# apricot.net
KiCad netlist of a schematic drawn in EAGLE
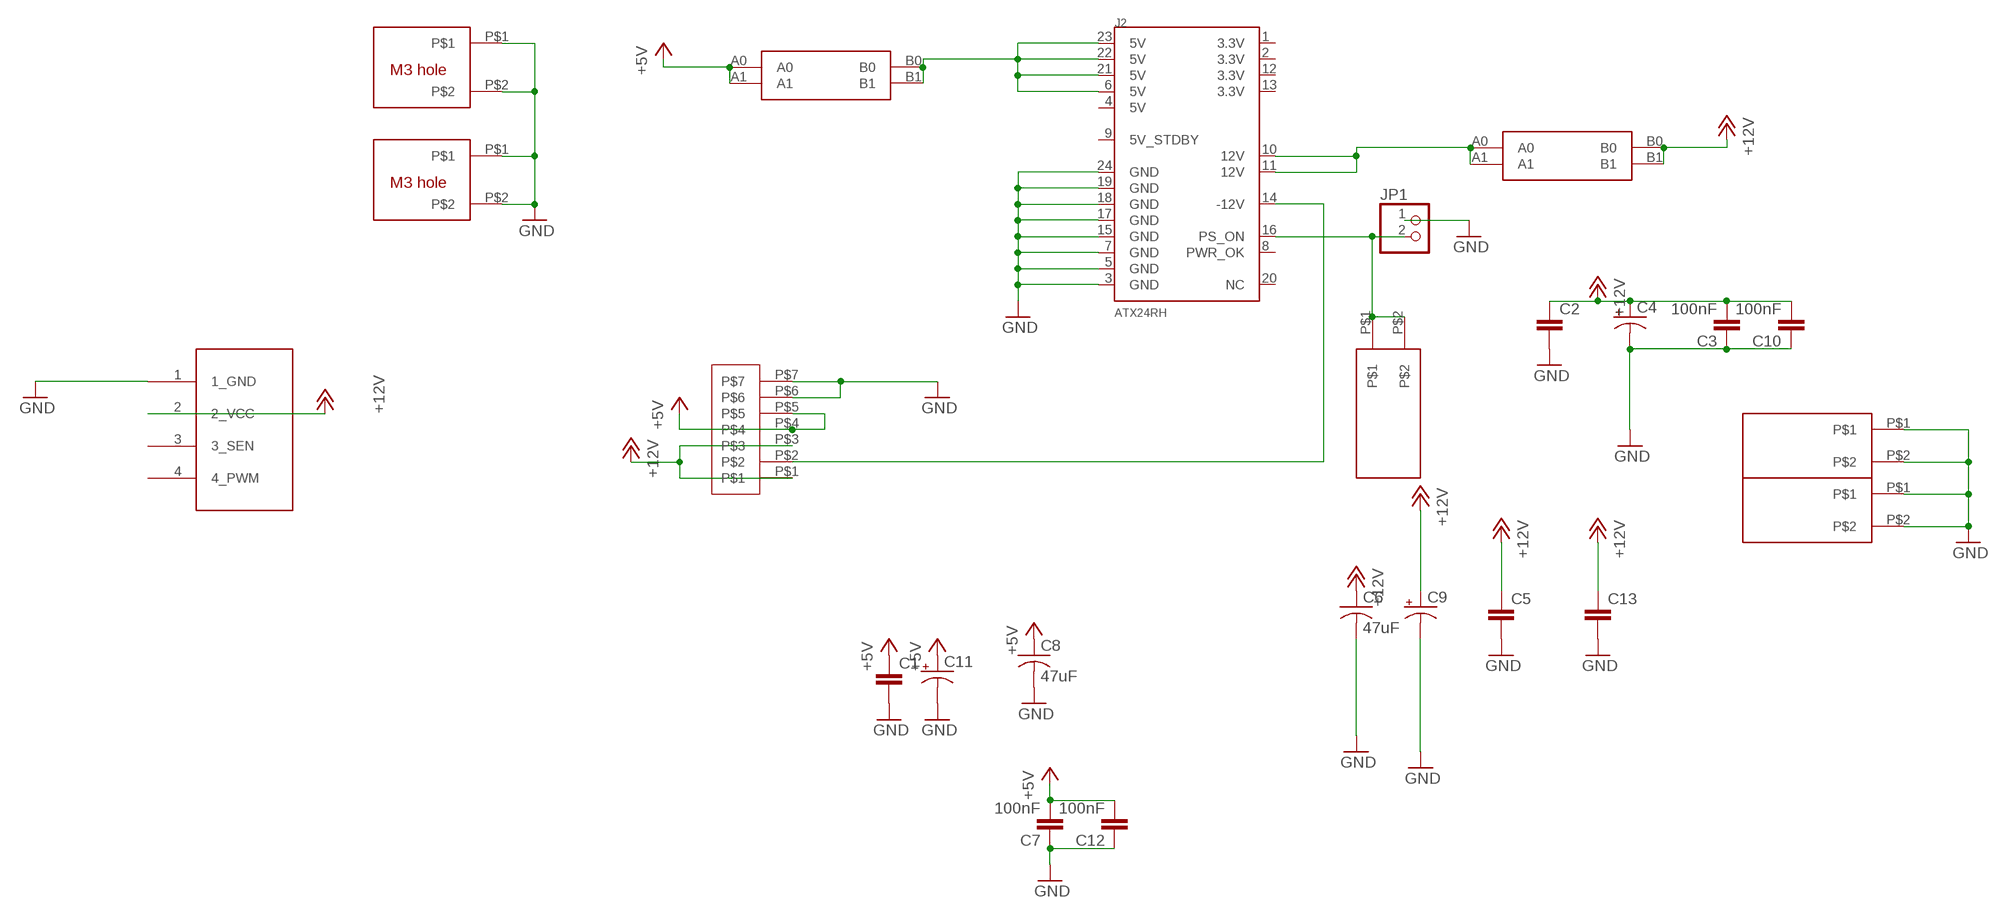
[diagram p0: schematic, sheet 1]

(export (version "E")
  (design (tool "Eeschema 10.0.6"))
  (components
    (comp (ref "C1")
      (value "C5/2.5")
      (footprint "eagle-import:C5B2.5")
      (libsource (lib "eagle-import") (part "C5/2.5"))
    )
    (comp (ref "C2")
      (value "C5/2.5")
      (footprint "eagle-import:C5B2.5")
      (libsource (lib "eagle-import") (part "C5/2.5"))
    )
    (comp (ref "C3")
      (value "100nF")
      (footprint "eagle-import:0805@1")
      (libsource (lib "eagle-import") (part "CAP0805"))
    )
    (comp (ref "C4")
      (value "CPOL-USE3.5-8")
      (footprint "eagle-import:E3,5-8")
      (libsource (lib "eagle-import") (part "CPOL-USE3.5-8"))
    )
    (comp (ref "C5")
      (value "C5/2.5")
      (footprint "eagle-import:C5B2.5")
      (libsource (lib "eagle-import") (part "C5/2.5"))
    )
    (comp (ref "C6")
      (value "47uF")
      (footprint "eagle-import:C1210")
      (libsource (lib "eagle-import") (part "C-USC1210"))
    )
    (comp (ref "C7")
      (value "100nF")
      (footprint "eagle-import:0805@1")
      (libsource (lib "eagle-import") (part "CAP0805"))
    )
    (comp (ref "C8")
      (value "47uF")
      (footprint "eagle-import:C1210")
      (libsource (lib "eagle-import") (part "C-USC1210"))
    )
    (comp (ref "C9")
      (value "CPOL-USE3.5-8")
      (footprint "eagle-import:E3,5-8")
      (libsource (lib "eagle-import") (part "CPOL-USE3.5-8"))
    )
    (comp (ref "C10")
      (value "100nF")
      (footprint "eagle-import:0805@1")
      (libsource (lib "eagle-import") (part "CAP0805"))
    )
    (comp (ref "C11")
      (value "CPOL-USE3.5-8")
      (footprint "eagle-import:E3,5-8")
      (libsource (lib "eagle-import") (part "CPOL-USE3.5-8"))
    )
    (comp (ref "C12")
      (value "100nF")
      (footprint "eagle-import:0805@1")
      (libsource (lib "eagle-import") (part "CAP0805"))
    )
    (comp (ref "C13")
      (value "C5/2.5")
      (footprint "eagle-import:C5B2.5")
      (libsource (lib "eagle-import") (part "C5/2.5"))
    )
    (comp (ref "J2")
      (value "ATX24RH")
      (footprint "eagle-import:ATX24_RIGHT_ANGLE")
      (libsource (lib "eagle-import") (part "ATX24RH"))
    )
    (comp (ref "JP1")
      (value "PINHD-1X2")
      (footprint "eagle-import:1X02")
      (libsource (lib "eagle-import") (part "PINHD-1X2"))
    )
    (comp (ref "JP3")
      (value "4PIN_FAN")
      (footprint "eagle-import:1X04")
      (libsource (lib "eagle-import") (part "4PIN_FAN"))
    )
    (comp (ref "U$1")
      (value "6MM_BLADE")
      (footprint "eagle-import:6.2MMBLADE")
      (libsource (lib "eagle-import") (part "6MM_BLADE"))
    )
    (comp (ref "U$2")
      (value "CAR_FUSE_HOLDER3IN1")
      (footprint "eagle-import:FUSE_HOLDER_3IN1")
      (libsource (lib "eagle-import") (part "CAR_FUSE_HOLDER3IN1"))
    )
    (comp (ref "U$3")
      (value "6MM_BLADE")
      (footprint "eagle-import:6.2MMBLADE")
      (libsource (lib "eagle-import") (part "6MM_BLADE"))
    )
    (comp (ref "U$4")
      (value "VH396")
      (footprint "eagle-import:396_7P")
      (libsource (lib "eagle-import") (part "VH396"))
    )
    (comp (ref "U$5")
      (value "M3_MOUNTING_HOLE")
      (footprint "eagle-import:M3_MOUNTING_HOLE_PACK")
      (libsource (lib "eagle-import") (part "M3_MOUNTING_HOLE"))
    )
    (comp (ref "U$6")
      (value "M3_MOUNTING_HOLE")
      (footprint "eagle-import:M3_MOUNTING_HOLE_PACK")
      (libsource (lib "eagle-import") (part "M3_MOUNTING_HOLE"))
    )
    (comp (ref "U$7")
      (value "6MM_BLADE")
      (footprint "eagle-import:6.2MMBLADE")
      (libsource (lib "eagle-import") (part "6MM_BLADE"))
    )
    (comp (ref "U$8")
      (value "CAR_FUSE_HOLDER3IN1")
      (footprint "eagle-import:FUSE_HOLDER_3IN1")
      (libsource (lib "eagle-import") (part "CAR_FUSE_HOLDER3IN1"))
    )
  )
  (nets
    (net (code "1") (name "+5V") (class "Default")
      (node (ref "C1") (pin "1") (pinfunction "1_1") (pintype "passive"))
      (node (ref "C11") (pin "+") (pinfunction "+_+") (pintype "passive"))
      (node (ref "C12") (pin "2") (pinfunction "2_2") (pintype "passive"))
      (node (ref "C7") (pin "2") (pinfunction "2_2") (pintype "passive"))
      (node (ref "C8") (pin "1") (pinfunction "1_1") (pintype "passive"))
      (node (ref "U$4") (pin "P$4") (pinfunction "P$4_P$4") (pintype "bidirectional"))
      (node (ref "U$4") (pin "P$5") (pinfunction "P$5_P$5") (pintype "bidirectional"))
      (node (ref "U$8") (pin "A0") (pinfunction "A0_A0") (pintype "bidirectional"))
      (node (ref "U$8") (pin "A1") (pinfunction "A1_A1") (pintype "bidirectional"))
    )
    (net (code "2") (name "+12V") (class "Default")
      (node (ref "C10") (pin "2") (pinfunction "2_2") (pintype "passive"))
      (node (ref "C13") (pin "1") (pinfunction "1_1") (pintype "passive"))
      (node (ref "C2") (pin "1") (pinfunction "1_1") (pintype "passive"))
      (node (ref "C3") (pin "2") (pinfunction "2_2") (pintype "passive"))
      (node (ref "C4") (pin "+") (pinfunction "+_+") (pintype "passive"))
      (node (ref "C5") (pin "1") (pinfunction "1_1") (pintype "passive"))
      (node (ref "C6") (pin "1") (pinfunction "1_1") (pintype "passive"))
      (node (ref "C9") (pin "+") (pinfunction "+_+") (pintype "passive"))
      (node (ref "JP3") (pin "2") (pinfunction "2_VCC_2") (pintype "passive"))
      (node (ref "U$2") (pin "B0") (pinfunction "B0_B0") (pintype "bidirectional"))
      (node (ref "U$2") (pin "B1") (pinfunction "B1_B1") (pintype "bidirectional"))
      (node (ref "U$4") (pin "P$1") (pinfunction "P$1_P$1") (pintype "bidirectional"))
      (node (ref "U$4") (pin "P$3") (pinfunction "P$3_P$3") (pintype "bidirectional"))
    )
    (net (code "3") (name "GND") (class "Default")
      (node (ref "C1") (pin "2") (pinfunction "2_2") (pintype "passive"))
      (node (ref "C10") (pin "1") (pinfunction "1_1") (pintype "passive"))
      (node (ref "C11") (pin "-") (pinfunction "-_-") (pintype "passive"))
      (node (ref "C12") (pin "1") (pinfunction "1_1") (pintype "passive"))
      (node (ref "C13") (pin "2") (pinfunction "2_2") (pintype "passive"))
      (node (ref "C2") (pin "2") (pinfunction "2_2") (pintype "passive"))
      (node (ref "C3") (pin "1") (pinfunction "1_1") (pintype "passive"))
      (node (ref "C4") (pin "-") (pinfunction "-_-") (pintype "passive"))
      (node (ref "C5") (pin "2") (pinfunction "2_2") (pintype "passive"))
      (node (ref "C6") (pin "2") (pinfunction "2_2") (pintype "passive"))
      (node (ref "C7") (pin "1") (pinfunction "1_1") (pintype "passive"))
      (node (ref "C8") (pin "2") (pinfunction "2_2") (pintype "passive"))
      (node (ref "C9") (pin "-") (pinfunction "-_-") (pintype "passive"))
      (node (ref "J2") (pin "15") (pinfunction "GND_15") (pintype "bidirectional"))
      (node (ref "J2") (pin "17") (pinfunction "GND_17") (pintype "bidirectional"))
      (node (ref "J2") (pin "18") (pinfunction "GND_18") (pintype "bidirectional"))
      (node (ref "J2") (pin "19") (pinfunction "GND_19") (pintype "bidirectional"))
      (node (ref "J2") (pin "24") (pinfunction "GND_24") (pintype "bidirectional"))
      (node (ref "J2") (pin "3") (pinfunction "GND_3") (pintype "bidirectional"))
      (node (ref "J2") (pin "5") (pinfunction "GND_5") (pintype "bidirectional"))
      (node (ref "J2") (pin "7") (pinfunction "GND_7") (pintype "bidirectional"))
      (node (ref "JP1") (pin "1") (pinfunction "1_1") (pintype "passive"))
      (node (ref "JP3") (pin "1") (pinfunction "1_GND_1") (pintype "passive"))
      (node (ref "U$3") (pin "P$1") (pinfunction "P$1_P$1") (pintype "bidirectional"))
      (node (ref "U$3") (pin "P$2") (pinfunction "P$2_P$2") (pintype "bidirectional"))
      (node (ref "U$4") (pin "P$6") (pinfunction "P$6_P$6") (pintype "bidirectional"))
      (node (ref "U$4") (pin "P$7") (pinfunction "P$7_P$7") (pintype "bidirectional"))
      (node (ref "U$5") (pin "P$1") (pinfunction "P$1_P$1") (pintype "bidirectional"))
      (node (ref "U$5") (pin "P$2") (pinfunction "P$2_P$2") (pintype "bidirectional"))
      (node (ref "U$6") (pin "P$1") (pinfunction "P$1_P$1") (pintype "bidirectional"))
      (node (ref "U$6") (pin "P$2") (pinfunction "P$2_P$2") (pintype "bidirectional"))
      (node (ref "U$7") (pin "P$1") (pinfunction "P$1_P$1") (pintype "bidirectional"))
      (node (ref "U$7") (pin "P$2") (pinfunction "P$2_P$2") (pintype "bidirectional"))
    )
    (net (code "4") (name "Net-(J2--12V)") (class "Default")
      (node (ref "J2") (pin "14") (pinfunction "-12V_14") (pintype "bidirectional"))
      (node (ref "U$4") (pin "P$2") (pinfunction "P$2_P$2") (pintype "bidirectional"))
    )
    (net (code "5") (name "Net-(J2-5V-Pad21)") (class "Default")
      (node (ref "J2") (pin "21") (pinfunction "5V_21") (pintype "bidirectional"))
      (node (ref "J2") (pin "22") (pinfunction "5V_22") (pintype "bidirectional"))
      (node (ref "J2") (pin "23") (pinfunction "5V_23") (pintype "bidirectional"))
      (node (ref "J2") (pin "6") (pinfunction "5V_6") (pintype "bidirectional"))
      (node (ref "U$8") (pin "B0") (pinfunction "B0_B0") (pintype "bidirectional"))
      (node (ref "U$8") (pin "B1") (pinfunction "B1_B1") (pintype "bidirectional"))
    )
    (net (code "6") (name "Net-(J2-12V-Pad10)") (class "Default")
      (node (ref "J2") (pin "10") (pinfunction "12V_10") (pintype "bidirectional"))
      (node (ref "J2") (pin "11") (pinfunction "12V_11") (pintype "bidirectional"))
      (node (ref "U$2") (pin "A0") (pinfunction "A0_A0") (pintype "bidirectional"))
      (node (ref "U$2") (pin "A1") (pinfunction "A1_A1") (pintype "bidirectional"))
    )
    (net (code "7") (name "Net-(J2-PS_ON)") (class "Default")
      (node (ref "J2") (pin "16") (pinfunction "PS_ON_16") (pintype "bidirectional"))
      (node (ref "JP1") (pin "2") (pinfunction "2_2") (pintype "passive"))
      (node (ref "U$1") (pin "P$1") (pinfunction "P$1_P$1") (pintype "bidirectional"))
      (node (ref "U$1") (pin "P$2") (pinfunction "P$2_P$2") (pintype "bidirectional"))
    )
    (net (code "8") (name "unconnected-(J2-3.3V-Pad1)") (class "Default")
      (node (ref "J2") (pin "1") (pinfunction "3.3V_1") (pintype "bidirectional"))
    )
    (net (code "9") (name "unconnected-(J2-3.3V-Pad2)") (class "Default")
      (node (ref "J2") (pin "2") (pinfunction "3.3V_2") (pintype "bidirectional"))
    )
    (net (code "10") (name "unconnected-(J2-3.3V-Pad12)") (class "Default")
      (node (ref "J2") (pin "12") (pinfunction "3.3V_12") (pintype "bidirectional"))
    )
    (net (code "11") (name "unconnected-(J2-3.3V-Pad13)") (class "Default")
      (node (ref "J2") (pin "13") (pinfunction "3.3V_13") (pintype "bidirectional"))
    )
    (net (code "12") (name "unconnected-(J2-5V-Pad4)") (class "Default")
      (node (ref "J2") (pin "4") (pinfunction "5V_4") (pintype "bidirectional"))
    )
    (net (code "13") (name "unconnected-(J2-5V_STDBY-Pad9)") (class "Default")
      (node (ref "J2") (pin "9") (pinfunction "5V_STDBY_9") (pintype "bidirectional"))
    )
    (net (code "14") (name "unconnected-(J2-NC-Pad20)") (class "Default")
      (node (ref "J2") (pin "20") (pinfunction "NC_20") (pintype "bidirectional"))
    )
    (net (code "15") (name "unconnected-(J2-PWR_OK-Pad8)") (class "Default")
      (node (ref "J2") (pin "8") (pinfunction "PWR_OK_8") (pintype "bidirectional"))
    )
    (net (code "16") (name "unconnected-(JP3-3_SEN-Pad3)") (class "Default")
      (node (ref "JP3") (pin "3") (pinfunction "3_SEN_3") (pintype "passive"))
    )
    (net (code "17") (name "unconnected-(JP3-4_PWM-Pad4)") (class "Default")
      (node (ref "JP3") (pin "4") (pinfunction "4_PWM_4") (pintype "passive"))
    )
  )
)
